# bitsClassic.net
KiCad netlist of a schematic drawn in EAGLE
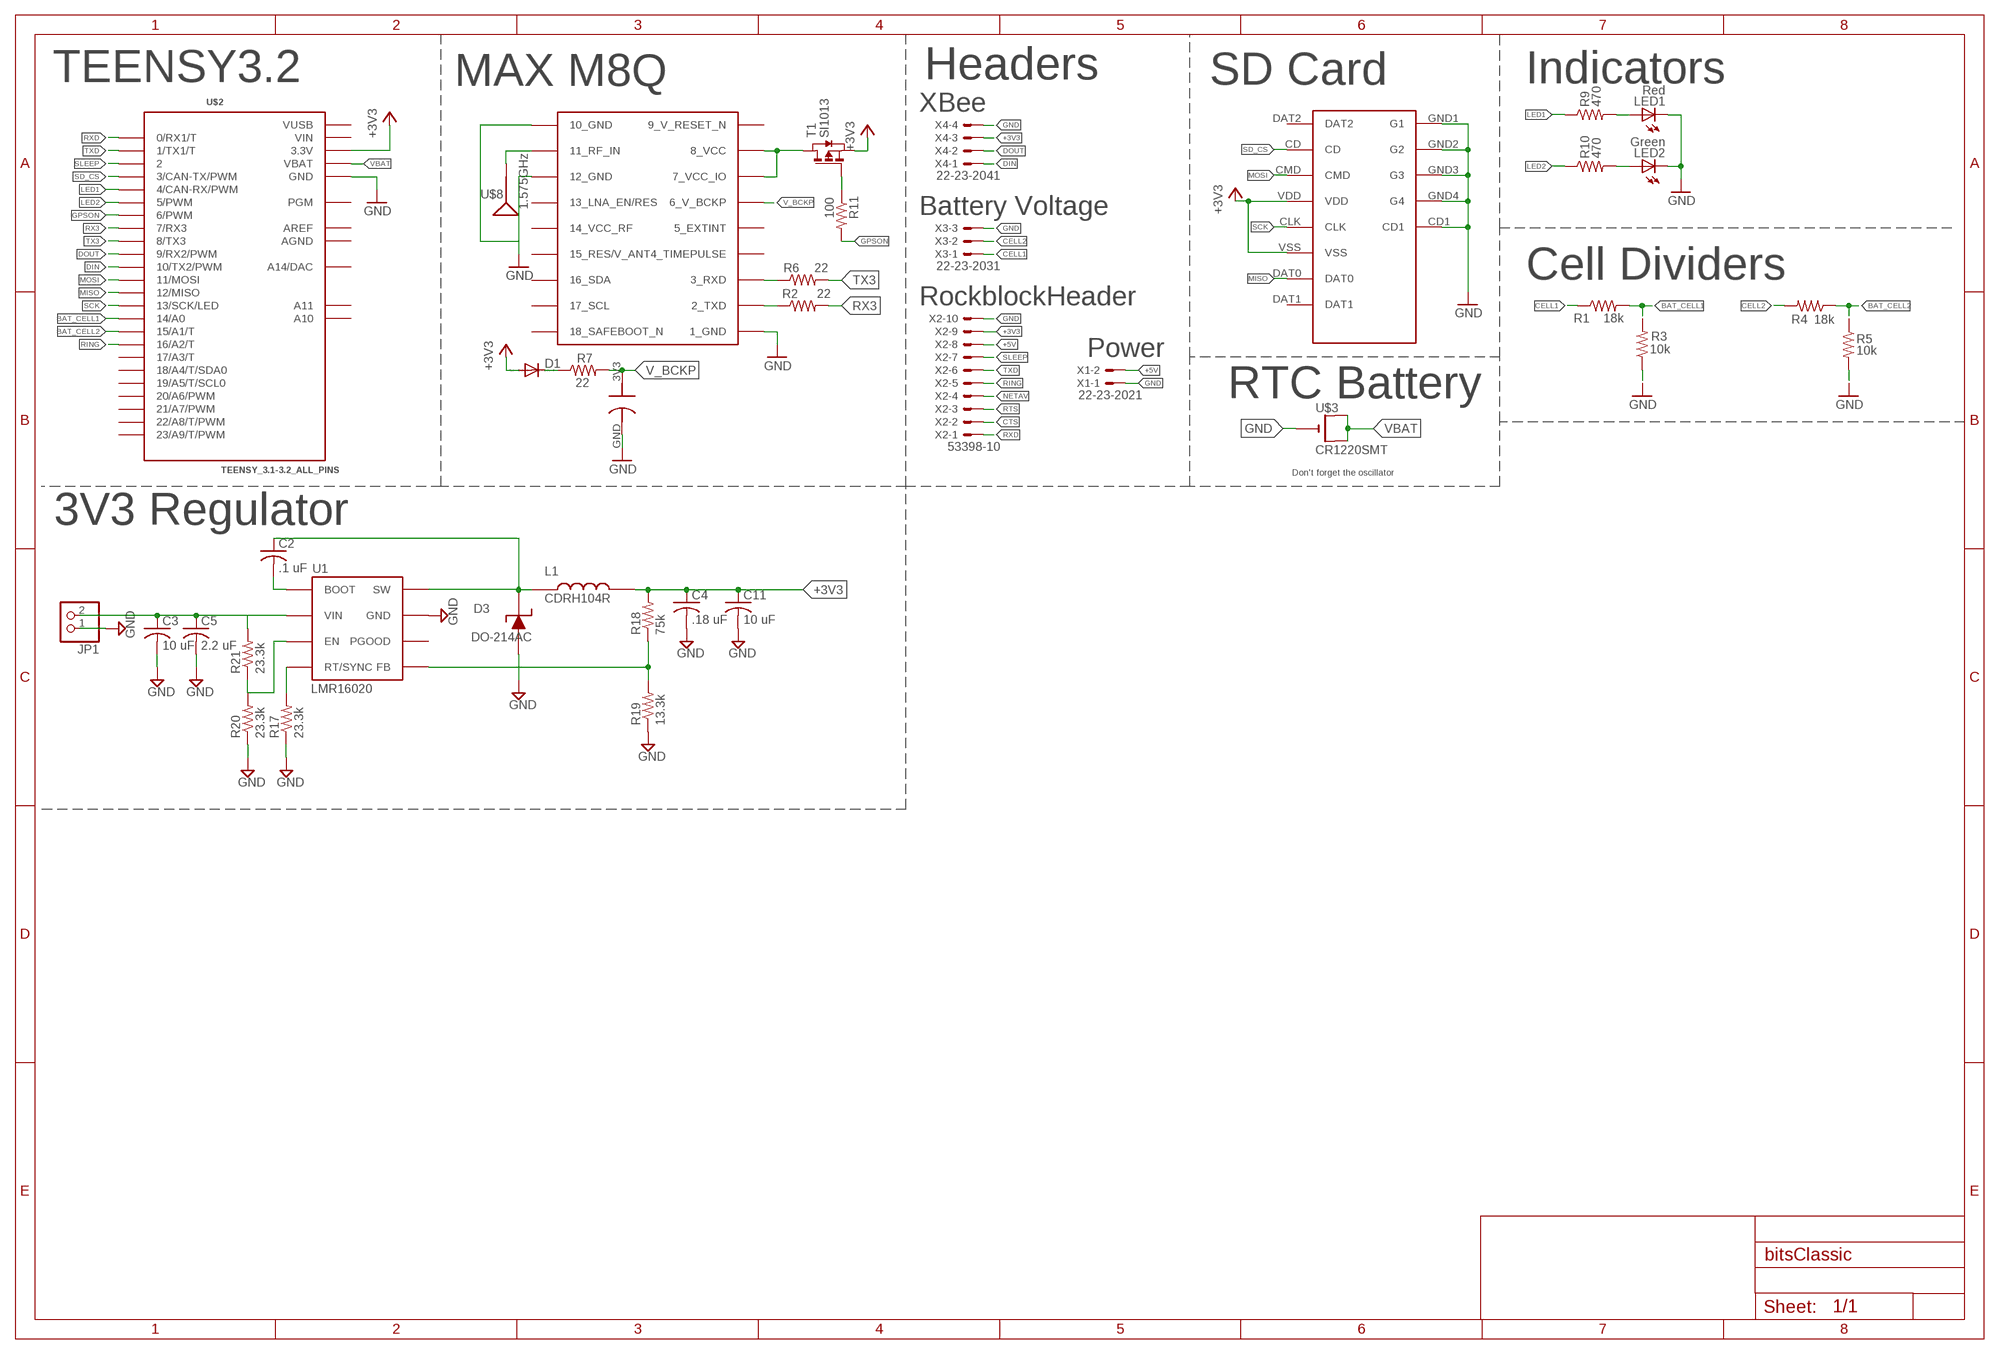
[diagram p0: schematic, sheet 1]

(export (version "E")
  (design (tool "Eeschema 10.0.6"))
  (components
    (comp (ref "C1")
      (value "DCK-3R3E204T614-E")
      (footprint "eagle-import:ELNASUPERCAP")
      (libsource (lib "eagle-import") (part "DCK-3R3E204T614-E"))
    )
    (comp (ref "C2")
      (value ".1 uF")
      (footprint "eagle-import:C0603")
      (libsource (lib "eagle-import") (part "C-USC0603"))
    )
    (comp (ref "C3")
      (value "10 uF")
      (footprint "eagle-import:C1210")
      (libsource (lib "eagle-import") (part "C-USC1210"))
    )
    (comp (ref "C4")
      (value ".18 uF")
      (footprint "eagle-import:C0603")
      (libsource (lib "eagle-import") (part "C-USC0603"))
    )
    (comp (ref "C5")
      (value "2.2 uF")
      (footprint "eagle-import:C1210")
      (libsource (lib "eagle-import") (part "C-USC1210"))
    )
    (comp (ref "C11")
      (value "10 uF")
      (footprint "eagle-import:C0603")
      (libsource (lib "eagle-import") (part "C-USC0603"))
    )
    (comp (ref "D1")
      (value "DIODE-SOD523")
      (footprint "eagle-import:SOD523")
      (libsource (lib "eagle-import") (part "DIODE-SOD523"))
    )
    (comp (ref "D3")
      (value "DO-214AC")
      (footprint "eagle-import:DO-214AC")
      (libsource (lib "eagle-import") (part "DO-214AC"))
    )
    (comp (ref "JP1")
      (value "PINHD-1X2")
      (footprint "eagle-import:1X02")
      (libsource (lib "eagle-import") (part "PINHD-1X2"))
    )
    (comp (ref "L1")
      (value "CDRH104R")
      (footprint "eagle-import:CDRH104R")
      (libsource (lib "eagle-import") (part "CDRH104R"))
    )
    (comp (ref "LED1")
      (value "Red")
      (footprint "eagle-import:CHIP-LED0603")
      (libsource (lib "eagle-import") (part "LEDCHIP-LED0603"))
    )
    (comp (ref "LED2")
      (value "Green")
      (footprint "eagle-import:CHIP-LED0603")
      (libsource (lib "eagle-import") (part "LEDCHIP-LED0603"))
    )
    (comp (ref "R1")
      (value "18k")
      (footprint "eagle-import:R0603")
      (libsource (lib "eagle-import") (part "resistor_R-US_R0603"))
    )
    (comp (ref "R2")
      (value "22")
      (footprint "eagle-import:R0603")
      (libsource (lib "eagle-import") (part "R-US_R0603"))
    )
    (comp (ref "R3")
      (value "10k")
      (footprint "eagle-import:R0603")
      (libsource (lib "eagle-import") (part "resistor_R-US_R0603"))
    )
    (comp (ref "R4")
      (value "18k")
      (footprint "eagle-import:R0603")
      (libsource (lib "eagle-import") (part "resistor_R-US_R0603"))
    )
    (comp (ref "R5")
      (value "10k")
      (footprint "eagle-import:R0603")
      (libsource (lib "eagle-import") (part "resistor_R-US_R0603"))
    )
    (comp (ref "R6")
      (value "22")
      (footprint "eagle-import:R0603")
      (libsource (lib "eagle-import") (part "R-US_R0603"))
    )
    (comp (ref "R7")
      (value "22")
      (footprint "eagle-import:R0603")
      (libsource (lib "eagle-import") (part "R-US_R0603"))
    )
    (comp (ref "R9")
      (value "470")
      (footprint "eagle-import:R0603")
      (libsource (lib "eagle-import") (part "resistor_R-US_R0603"))
    )
    (comp (ref "R10")
      (value "470")
      (footprint "eagle-import:R0603")
      (libsource (lib "eagle-import") (part "resistor_R-US_R0603"))
    )
    (comp (ref "R11")
      (value "100")
      (footprint "eagle-import:R0603")
      (libsource (lib "eagle-import") (part "R-US_R0603"))
    )
    (comp (ref "R17")
      (value "23.3k")
      (footprint "eagle-import:R0603")
      (libsource (lib "eagle-import") (part "resistor_R-US_R0603"))
    )
    (comp (ref "R18")
      (value "75k")
      (footprint "eagle-import:R0603")
      (libsource (lib "eagle-import") (part "resistor_R-US_R0603"))
    )
    (comp (ref "R19")
      (value "13.3k")
      (footprint "eagle-import:R0603")
      (libsource (lib "eagle-import") (part "resistor_R-US_R0603"))
    )
    (comp (ref "R20")
      (value "23.3k")
      (footprint "eagle-import:R0603")
      (libsource (lib "eagle-import") (part "resistor_R-US_R0603"))
    )
    (comp (ref "R21")
      (value "23.3k")
      (footprint "eagle-import:R0603")
      (libsource (lib "eagle-import") (part "resistor_R-US_R0603"))
    )
    (comp (ref "T1")
      (value "SI1013")
      (footprint "eagle-import:SC-75")
      (libsource (lib "eagle-import") (part "SI1013"))
    )
    (comp (ref "U$2")
      (value "TEENSY_3.1-3.2_ALL_PINS")
      (footprint "eagle-import:TEENSY_3.0-3.2&LC_ALL_PINS")
      (libsource (lib "eagle-import") (part "TEENSY_3.1-3.2_ALL_PINS"))
    )
    (comp (ref "U$3")
      (value "CR1220SMT")
      (footprint "eagle-import:CR1220-SMD")
      (libsource (lib "eagle-import") (part "CR1220SMT"))
    )
    (comp (ref "U$4")
      (value "MICRO_SD")
      (footprint "eagle-import:MICRO_SD_HINGED")
      (libsource (lib "eagle-import") (part "MICRO_SD"))
    )
    (comp (ref "U$7")
      (value "MAX-M8")
      (footprint "eagle-import:MAX-M8")
      (libsource (lib "eagle-import") (part "MAX-M8"))
    )
    (comp (ref "U$8")
      (value "1.575GHz")
      (footprint "eagle-import:SPARKFUN-GPS_ANT-GPS-2X7MM")
      (libsource (lib "eagle-import") (part "SPARKFUN-GPS_ANTENNAGPS-2X7MM"))
    )
    (comp (ref "U1")
      (value "LMR16020")
      (footprint "eagle-import:SO8")
      (libsource (lib "eagle-import") (part "LMR16020"))
    )
    (comp (ref "X1")
      (value "22-23-2021")
      (footprint "eagle-import:22-23-2021")
      (fields (field (name "MF") "MOLEX"))
      (libsource (lib "eagle-import") (part "22-23-2021"))
    )
    (comp (ref "X2")
      (value "53398-10")
      (footprint "eagle-import:53398-10")
      (fields (field (name "MF") "MOLEX") (field (name "MPN") "53398-1071"))
      (libsource (lib "eagle-import") (part "53?-10398"))
    )
    (comp (ref "X3")
      (value "22-23-2031")
      (footprint "eagle-import:22-23-2031")
      (fields (field (name "MF") "MOLEX"))
      (libsource (lib "eagle-import") (part "22-23-2031"))
    )
    (comp (ref "X4")
      (value "22-23-2041")
      (footprint "eagle-import:22-23-2041")
      (fields (field (name "MF") "MOLEX"))
      (libsource (lib "eagle-import") (part "22-23-2041"))
    )
  )
  (nets
    (net (code "1") (name "+3V3") (class "Default")
      (node (ref "C11") (pin "1") (pinfunction "1_1") (pintype "passive"))
      (node (ref "C4") (pin "1") (pinfunction "1_1") (pintype "passive"))
      (node (ref "D1") (pin "A") (pinfunction "A_A") (pintype "passive"))
      (node (ref "L1") (pin "P$2") (pinfunction "P$2_P$2") (pintype "bidirectional"))
      (node (ref "R18") (pin "2") (pinfunction "2_2") (pintype "passive"))
      (node (ref "T1") (pin "P$2") (pinfunction "S_P$2") (pintype "passive"))
      (node (ref "U$2") (pin "3.3V") (pinfunction "3.3V_3.3V") (pintype "power_in"))
      (node (ref "U$2") (pin "3.3V1") (pinfunction "3.3V_3.3V1") (pintype "power_in"))
      (node (ref "U$4") (pin "VDD") (pinfunction "VDD_VDD") (pintype "bidirectional"))
      (node (ref "U$4") (pin "VSS") (pinfunction "VSS_VSS") (pintype "bidirectional"))
      (node (ref "X2") (pin "9") (pinfunction "S_9") (pintype "passive"))
      (node (ref "X4") (pin "3") (pinfunction "S_3") (pintype "passive"))
    )
    (net (code "2") (name "+5V") (class "Default")
      (node (ref "X1") (pin "2") (pinfunction "S_2") (pintype "passive"))
      (node (ref "X2") (pin "8") (pinfunction "S_8") (pintype "passive"))
    )
    (net (code "3") (name "/9_V_RESET_N") (class "Default")
      (node (ref "U$7") (pin "9_RESET_N") (pinfunction "9_V_RESET_N_9_RESET_N") (pintype "power_in"))
    )
    (net (code "4") (name "/AGND") (class "Default")
      (node (ref "U$2") (pin "AGND") (pinfunction "AGND_AGND") (pintype "power_in"))
    )
    (net (code "5") (name "/AREF") (class "Default")
      (node (ref "U$2") (pin "AREF") (pinfunction "AREF_AREF") (pintype "power_in"))
    )
    (net (code "6") (name "/VIN") (class "Default")
      (node (ref "U$2") (pin "VIN") (pinfunction "VIN_VIN") (pintype "power_in"))
    )
    (net (code "7") (name "/VUSB") (class "Default")
      (node (ref "U$2") (pin "VUSB") (pinfunction "VUSB_VUSB") (pintype "power_in"))
    )
    (net (code "8") (name "BAT_CELL1") (class "Default")
      (node (ref "R1") (pin "2") (pinfunction "2_2") (pintype "passive"))
      (node (ref "R3") (pin "2") (pinfunction "2_2") (pintype "passive"))
      (node (ref "U$2") (pin "14/A0") (pinfunction "14/A0_14/A0") (pintype "bidirectional"))
    )
    (net (code "9") (name "BAT_CELL2") (class "Default")
      (node (ref "R4") (pin "1") (pinfunction "1_1") (pintype "passive"))
      (node (ref "R5") (pin "1") (pinfunction "1_1") (pintype "passive"))
      (node (ref "U$2") (pin "15/A1") (pinfunction "15/A1/T_15/A1") (pintype "bidirectional"))
    )
    (net (code "10") (name "CELL1") (class "Default")
      (node (ref "R1") (pin "1") (pinfunction "1_1") (pintype "passive"))
      (node (ref "X3") (pin "1") (pinfunction "S_1") (pintype "passive"))
    )
    (net (code "11") (name "CELL2") (class "Default")
      (node (ref "R4") (pin "2") (pinfunction "2_2") (pintype "passive"))
      (node (ref "X3") (pin "2") (pinfunction "S_2") (pintype "passive"))
    )
    (net (code "12") (name "CTS") (class "Default")
      (node (ref "X2") (pin "2") (pinfunction "S_2") (pintype "passive"))
    )
    (net (code "13") (name "DIN") (class "Default")
      (node (ref "U$2") (pin "10") (pinfunction "10/TX2/PWM_10") (pintype "bidirectional"))
      (node (ref "X4") (pin "1") (pinfunction "S_1") (pintype "passive"))
    )
    (net (code "14") (name "DOUT") (class "Default")
      (node (ref "U$2") (pin "9") (pinfunction "9/RX2/PWM_9") (pintype "bidirectional"))
      (node (ref "X4") (pin "2") (pinfunction "S_2") (pintype "passive"))
    )
    (net (code "15") (name "GND") (class "Default")
      (node (ref "C1") (pin "GND") (pinfunction "GND_GND") (pintype "bidirectional"))
      (node (ref "C11") (pin "2") (pinfunction "2_2") (pintype "passive"))
      (node (ref "C3") (pin "2") (pinfunction "2_2") (pintype "passive"))
      (node (ref "C4") (pin "2") (pinfunction "2_2") (pintype "passive"))
      (node (ref "C5") (pin "2") (pinfunction "2_2") (pintype "passive"))
      (node (ref "D3") (pin "P$1") (pinfunction "P$1_P$1") (pintype "bidirectional"))
      (node (ref "JP1") (pin "1") (pinfunction "1_1") (pintype "passive"))
      (node (ref "LED1") (pin "C") (pinfunction "C_C") (pintype "passive"))
      (node (ref "LED2") (pin "C") (pinfunction "C_C") (pintype "passive"))
      (node (ref "R17") (pin "1") (pinfunction "1_1") (pintype "passive"))
      (node (ref "R19") (pin "1") (pinfunction "1_1") (pintype "passive"))
      (node (ref "R20") (pin "1") (pinfunction "1_1") (pintype "passive"))
      (node (ref "R3") (pin "1") (pinfunction "1_1") (pintype "passive"))
      (node (ref "R5") (pin "2") (pinfunction "2_2") (pintype "passive"))
      (node (ref "U$2") (pin "GND") (pinfunction "GND_GND") (pintype "power_in"))
      (node (ref "U$2") (pin "GND1") (pinfunction "GND_GND1") (pintype "power_in"))
      (node (ref "U$3") (pin "-") (pinfunction "-_-") (pintype "passive"))
      (node (ref "U$4") (pin "CD1") (pinfunction "CD1_CD1") (pintype "bidirectional"))
      (node (ref "U$4") (pin "GND1") (pinfunction "G1_GND1") (pintype "bidirectional"))
      (node (ref "U$4") (pin "GND2") (pinfunction "G2_GND2") (pintype "bidirectional"))
      (node (ref "U$4") (pin "GND3") (pinfunction "G3_GND3") (pintype "bidirectional"))
      (node (ref "U$4") (pin "GND4") (pinfunction "G4_GND4") (pintype "bidirectional"))
      (node (ref "U$7") (pin "10_GND") (pinfunction "10_GND_10_GND") (pintype "power_in"))
      (node (ref "U$7") (pin "12_GND") (pinfunction "12_GND_12_GND") (pintype "power_in"))
      (node (ref "U$7") (pin "1_GND") (pinfunction "1_GND_1_GND") (pintype "power_in"))
      (node (ref "U1") (pin "P$7") (pinfunction "GND_P$7") (pintype "bidirectional"))
      (node (ref "U1") (pin "PAD") (pinfunction "GND_PAD") (pintype "bidirectional"))
      (node (ref "X1") (pin "1") (pinfunction "S_1") (pintype "passive"))
      (node (ref "X2") (pin "10") (pinfunction "S_10") (pintype "passive"))
      (node (ref "X3") (pin "3") (pinfunction "S_3") (pintype "passive"))
      (node (ref "X4") (pin "4") (pinfunction "S_4") (pintype "passive"))
    )
    (net (code "16") (name "GPSON") (class "Default")
      (node (ref "R11") (pin "2") (pinfunction "2_2") (pintype "passive"))
      (node (ref "U$2") (pin "6") (pinfunction "6/PWM_6") (pintype "bidirectional"))
    )
    (net (code "17") (name "LED1") (class "Default")
      (node (ref "R9") (pin "1") (pinfunction "1_1") (pintype "passive"))
      (node (ref "U$2") (pin "4") (pinfunction "4/CAN-RX/PWM_4") (pintype "bidirectional"))
    )
    (net (code "18") (name "LED2") (class "Default")
      (node (ref "R10") (pin "1") (pinfunction "1_1") (pintype "passive"))
      (node (ref "U$2") (pin "5") (pinfunction "5/PWM_5") (pintype "bidirectional"))
    )
    (net (code "19") (name "MISO") (class "Default")
      (node (ref "U$2") (pin "12") (pinfunction "12/MISO_12") (pintype "bidirectional"))
      (node (ref "U$4") (pin "DAT0") (pinfunction "DAT0_DAT0") (pintype "bidirectional"))
    )
    (net (code "20") (name "MOSI") (class "Default")
      (node (ref "U$2") (pin "11") (pinfunction "11/MOSI_11") (pintype "bidirectional"))
      (node (ref "U$4") (pin "CMD") (pinfunction "CMD_CMD") (pintype "bidirectional"))
    )
    (net (code "21") (name "NETAV") (class "Default")
      (node (ref "X2") (pin "4") (pinfunction "S_4") (pintype "passive"))
    )
    (net (code "22") (name "Net-(D1-PadC)") (class "Default")
      (node (ref "D1") (pin "C") (pinfunction "C_C") (pintype "passive"))
      (node (ref "R7") (pin "1") (pinfunction "1_1") (pintype "passive"))
    )
    (net (code "23") (name "Net-(LED1-PadA)") (class "Default")
      (node (ref "LED1") (pin "A") (pinfunction "A_A") (pintype "passive"))
      (node (ref "R9") (pin "2") (pinfunction "2_2") (pintype "passive"))
    )
    (net (code "24") (name "Net-(LED2-PadA)") (class "Default")
      (node (ref "LED2") (pin "A") (pinfunction "A_A") (pintype "passive"))
      (node (ref "R10") (pin "2") (pinfunction "2_2") (pintype "passive"))
    )
    (net (code "25") (name "Net-(R2-Pad1)") (class "Default")
      (node (ref "R2") (pin "1") (pinfunction "1_1") (pintype "passive"))
      (node (ref "U$7") (pin "2_TXD") (pinfunction "2_TXD_2_TXD") (pintype "bidirectional"))
    )
    (net (code "26") (name "Net-(R6-Pad1)") (class "Default")
      (node (ref "R6") (pin "1") (pinfunction "1_1") (pintype "passive"))
      (node (ref "U$7") (pin "3_RXD") (pinfunction "3_RXD_3_RXD") (pintype "bidirectional"))
    )
    (net (code "27") (name "Net-(T1-D)") (class "Default")
      (node (ref "T1") (pin "P$3") (pinfunction "D_P$3") (pintype "passive"))
      (node (ref "U$7") (pin "7_VCC_IO") (pinfunction "7_VCC_IO_7_VCC_IO") (pintype "power_in"))
      (node (ref "U$7") (pin "8_VCC") (pinfunction "8_VCC_8_VCC") (pintype "power_in"))
    )
    (net (code "28") (name "Net-(T1-G)") (class "Default")
      (node (ref "R11") (pin "1") (pinfunction "1_1") (pintype "passive"))
      (node (ref "T1") (pin "P$1") (pinfunction "G_P$1") (pintype "passive"))
    )
    (net (code "29") (name "Net-(U$8-SIGNAL)") (class "Default")
      (node (ref "U$7") (pin "11_RF_IN") (pinfunction "11_RF_IN_11_RF_IN") (pintype "bidirectional"))
      (node (ref "U$8") (pin "1") (pinfunction "SIGNAL_1") (pintype "bidirectional"))
    )
    (net (code "30") (name "Net-(U1-BOOT)") (class "Default")
      (node (ref "C2") (pin "2") (pinfunction "2_2") (pintype "passive"))
      (node (ref "U1") (pin "P$1") (pinfunction "BOOT_P$1") (pintype "bidirectional"))
    )
    (net (code "31") (name "Net-(U1-EN)") (class "Default")
      (node (ref "R20") (pin "2") (pinfunction "2_2") (pintype "passive"))
      (node (ref "R21") (pin "1") (pinfunction "1_1") (pintype "passive"))
      (node (ref "U1") (pin "P$3") (pinfunction "EN_P$3") (pintype "bidirectional"))
    )
    (net (code "32") (name "Net-(U1-FB)") (class "Default")
      (node (ref "R18") (pin "1") (pinfunction "1_1") (pintype "passive"))
      (node (ref "R19") (pin "2") (pinfunction "2_2") (pintype "passive"))
      (node (ref "U1") (pin "P$5") (pinfunction "FB_P$5") (pintype "bidirectional"))
    )
    (net (code "33") (name "Net-(U1-RT{slash}SYNC)") (class "Default")
      (node (ref "R17") (pin "2") (pinfunction "2_2") (pintype "passive"))
      (node (ref "U1") (pin "P$4") (pinfunction "RT/SYNC_P$4") (pintype "bidirectional"))
    )
    (net (code "34") (name "Net-(U1-SW)") (class "Default")
      (node (ref "C2") (pin "1") (pinfunction "1_1") (pintype "passive"))
      (node (ref "D3") (pin "P$2") (pinfunction "P$2_P$2") (pintype "bidirectional"))
      (node (ref "L1") (pin "P$1") (pinfunction "P$1_P$1") (pintype "bidirectional"))
      (node (ref "U1") (pin "P$8") (pinfunction "SW_P$8") (pintype "bidirectional"))
    )
    (net (code "35") (name "Net-(U1-VIN)") (class "Default")
      (node (ref "C3") (pin "1") (pinfunction "1_1") (pintype "passive"))
      (node (ref "C5") (pin "1") (pinfunction "1_1") (pintype "passive"))
      (node (ref "JP1") (pin "2") (pinfunction "2_2") (pintype "passive"))
      (node (ref "R21") (pin "2") (pinfunction "2_2") (pintype "passive"))
      (node (ref "U1") (pin "P$2") (pinfunction "VIN_P$2") (pintype "bidirectional"))
    )
    (net (code "36") (name "RING") (class "Default")
      (node (ref "U$2") (pin "16/A2") (pinfunction "16/A2/T_16/A2") (pintype "bidirectional"))
      (node (ref "X2") (pin "5") (pinfunction "S_5") (pintype "passive"))
    )
    (net (code "37") (name "RTS") (class "Default")
      (node (ref "X2") (pin "3") (pinfunction "S_3") (pintype "passive"))
    )
    (net (code "38") (name "RX3") (class "Default")
      (node (ref "R2") (pin "2") (pinfunction "2_2") (pintype "passive"))
      (node (ref "U$2") (pin "7") (pinfunction "7/RX3_7") (pintype "bidirectional"))
    )
    (net (code "39") (name "RXD") (class "Default")
      (node (ref "U$2") (pin "0") (pinfunction "0/RX1/T_0") (pintype "bidirectional"))
      (node (ref "X2") (pin "1") (pinfunction "S_1") (pintype "passive"))
    )
    (net (code "40") (name "SCK") (class "Default")
      (node (ref "U$2") (pin "13") (pinfunction "13/SCK/LED_13") (pintype "bidirectional"))
      (node (ref "U$4") (pin "CLK") (pinfunction "CLK_CLK") (pintype "bidirectional"))
    )
    (net (code "41") (name "SD_CS") (class "Default")
      (node (ref "U$2") (pin "3") (pinfunction "3/CAN-TX/PWM_3") (pintype "bidirectional"))
      (node (ref "U$4") (pin "CD") (pinfunction "CD_CD") (pintype "bidirectional"))
    )
    (net (code "42") (name "SLEEP") (class "Default")
      (node (ref "U$2") (pin "2") (pinfunction "2_2") (pintype "bidirectional"))
      (node (ref "X2") (pin "7") (pinfunction "S_7") (pintype "passive"))
    )
    (net (code "43") (name "TX3") (class "Default")
      (node (ref "R6") (pin "2") (pinfunction "2_2") (pintype "passive"))
      (node (ref "U$2") (pin "8") (pinfunction "8/TX3_8") (pintype "bidirectional"))
    )
    (net (code "44") (name "TXD") (class "Default")
      (node (ref "U$2") (pin "1") (pinfunction "1/TX1/T_1") (pintype "bidirectional"))
      (node (ref "X2") (pin "6") (pinfunction "S_6") (pintype "passive"))
    )
    (net (code "45") (name "VBAT") (class "Default")
      (node (ref "U$2") (pin "VBAT") (pinfunction "VBAT_VBAT") (pintype "power_in"))
      (node (ref "U$3") (pin "+$1") (pinfunction "+_+$1") (pintype "passive"))
      (node (ref "U$3") (pin "+$2") (pinfunction "+1_+$2") (pintype "passive"))
    )
    (net (code "46") (name "V_BCKP") (class "Default")
      (node (ref "C1") (pin "3V3") (pinfunction "3V3_3V3") (pintype "bidirectional"))
      (node (ref "R7") (pin "2") (pinfunction "2_2") (pintype "passive"))
      (node (ref "U$7") (pin "6_V_BCKP") (pinfunction "6_V_BCKP_6_V_BCKP") (pintype "bidirectional"))
    )
    (net (code "47") (name "unconnected-(U$2-17{slash}A3{slash}T-Pad17{slash}A3)") (class "Default")
      (node (ref "U$2") (pin "17/A3") (pinfunction "17/A3/T_17/A3") (pintype "bidirectional"))
    )
    (net (code "48") (name "unconnected-(U$2-18{slash}A4{slash}T{slash}SDA0-Pad18{slash}A4)") (class "Default")
      (node (ref "U$2") (pin "18/A4") (pinfunction "18/A4/T/SDA0_18/A4") (pintype "bidirectional"))
    )
    (net (code "49") (name "unconnected-(U$2-19{slash}A5{slash}T{slash}SCL0-Pad19{slash}A5)") (class "Default")
      (node (ref "U$2") (pin "19/A5") (pinfunction "19/A5/T/SCL0_19/A5") (pintype "bidirectional"))
    )
    (net (code "50") (name "unconnected-(U$2-20{slash}A6{slash}PWM-Pad20{slash}A6)") (class "Default")
      (node (ref "U$2") (pin "20/A6") (pinfunction "20/A6/PWM_20/A6") (pintype "bidirectional"))
    )
    (net (code "51") (name "unconnected-(U$2-21{slash}A7{slash}PWM-Pad21{slash}A7)") (class "Default")
      (node (ref "U$2") (pin "21/A7") (pinfunction "21/A7/PWM_21/A7") (pintype "bidirectional"))
    )
    (net (code "52") (name "unconnected-(U$2-22{slash}A8{slash}T{slash}PWM-Pad22{slash}A8)") (class "Default")
      (node (ref "U$2") (pin "22/A8") (pinfunction "22/A8/T/PWM_22/A8") (pintype "bidirectional"))
    )
    (net (code "53") (name "unconnected-(U$2-23{slash}A9{slash}T{slash}PWM-Pad23{slash}A9)") (class "Default")
      (node (ref "U$2") (pin "23/A9") (pinfunction "23/A9/T/PWM_23/A9") (pintype "bidirectional"))
    )
    (net (code "54") (name "unconnected-(U$2-A14{slash}DAC-PadRESET{slash}DAC)") (class "Default")
      (node (ref "U$2") (pin "RESET/DAC") (pinfunction "A14/DAC_RESET/DAC") (pintype "bidirectional"))
    )
    (net (code "55") (name "unconnected-(U$2-PadA10)") (class "Default")
      (node (ref "U$2") (pin "A10") (pinfunction "A10_A10") (pintype "bidirectional"))
    )
    (net (code "56") (name "unconnected-(U$2-PadA11)") (class "Default")
      (node (ref "U$2") (pin "A11") (pinfunction "A11_A11") (pintype "bidirectional"))
    )
    (net (code "57") (name "unconnected-(U$2-PadPGM)") (class "Default")
      (node (ref "U$2") (pin "PGM") (pinfunction "PGM_PGM") (pintype "bidirectional"))
    )
    (net (code "58") (name "unconnected-(U$4-PadDAT1)") (class "Default")
      (node (ref "U$4") (pin "DAT1") (pinfunction "DAT1_DAT1") (pintype "bidirectional"))
    )
    (net (code "59") (name "unconnected-(U$4-PadDAT2)") (class "Default")
      (node (ref "U$4") (pin "DAT2") (pinfunction "DAT2_DAT2") (pintype "bidirectional"))
    )
    (net (code "60") (name "unconnected-(U$7-13_LNA_EN{slash}RES-Pad13_LNA_EN)") (class "Default")
      (node (ref "U$7") (pin "13_LNA_EN") (pinfunction "13_LNA_EN/RES_13_LNA_EN") (pintype "bidirectional"))
    )
    (net (code "61") (name "unconnected-(U$7-15_RES{slash}V_ANT-Pad15_V_ANT{slash}RESERVED)") (class "Default")
      (node (ref "U$7") (pin "15_V_ANT/RESERVED") (pinfunction "15_RES/V_ANT_15_V_ANT/RESERVED") (pintype "bidirectional"))
    )
    (net (code "62") (name "unconnected-(U$7-Pad4_TIMEPULSE)") (class "Default")
      (node (ref "U$7") (pin "4_TIMEPULSE") (pinfunction "4_TIMEPULSE_4_TIMEPULSE") (pintype "bidirectional"))
    )
    (net (code "63") (name "unconnected-(U$7-Pad5_EXTINT)") (class "Default")
      (node (ref "U$7") (pin "5_EXTINT") (pinfunction "5_EXTINT_5_EXTINT") (pintype "bidirectional"))
    )
    (net (code "64") (name "unconnected-(U$7-Pad14_VCC_RF)") (class "Default")
      (node (ref "U$7") (pin "14_VCC_RF") (pinfunction "14_VCC_RF_14_VCC_RF") (pintype "bidirectional"))
    )
    (net (code "65") (name "unconnected-(U$7-Pad16_SDA)") (class "Default")
      (node (ref "U$7") (pin "16_SDA") (pinfunction "16_SDA_16_SDA") (pintype "bidirectional"))
    )
    (net (code "66") (name "unconnected-(U$7-Pad17_SCL)") (class "Default")
      (node (ref "U$7") (pin "17_SCL") (pinfunction "17_SCL_17_SCL") (pintype "bidirectional"))
    )
    (net (code "67") (name "unconnected-(U$7-Pad18_SAFEBOOT_N)") (class "Default")
      (node (ref "U$7") (pin "18_SAFEBOOT_N") (pinfunction "18_SAFEBOOT_N_18_SAFEBOOT_N") (pintype "bidirectional"))
    )
    (net (code "68") (name "unconnected-(U1-PGOOD-PadP$6)") (class "Default")
      (node (ref "U1") (pin "P$6") (pinfunction "PGOOD_P$6") (pintype "bidirectional"))
    )
  )
)
